# AFE.net
KiCad netlist of a schematic drawn in Altium Designer
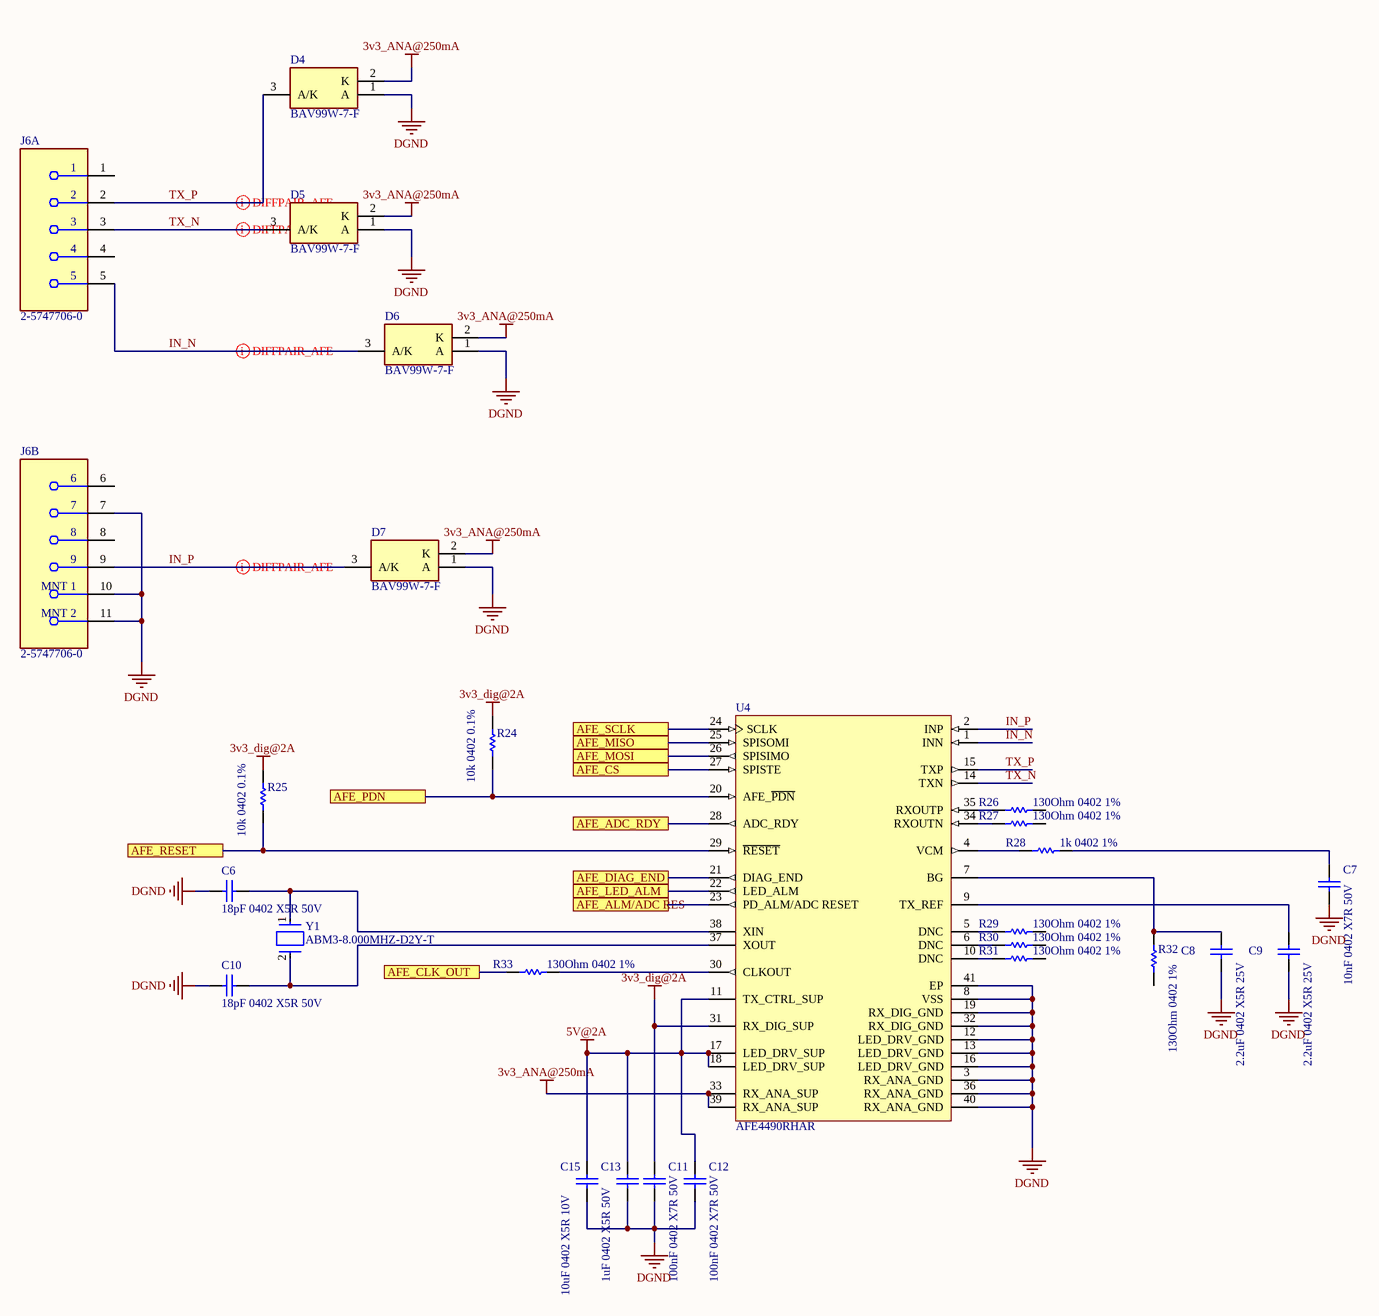
[diagram p0: AFE.SchDoc]

(export (version "E")
  (design (tool "Eeschema 10.0.6"))
  (components
    (comp (ref "C6")
      (value "18pF 0402 X5R 50V")
      (footprint "CAPC1005X55X25NL5T10")
      (libsource (lib "Altium Content Vault") (part "CAP-NP-2"))
    )
    (comp (ref "C7")
      (value "10nF 0402 X7R 50V")
      (footprint "CAPC1005X55X25NL5T10")
      (libsource (lib "Altium Content Vault") (part "CAP-NP-2"))
    )
    (comp (ref "C8")
      (value "2.2uF 0402 X5R 25V")
      (footprint "CAPC1005X55X25NL5T10")
      (libsource (lib "Altium Content Vault") (part "CAP-NP-2"))
    )
    (comp (ref "C9")
      (value "2.2uF 0402 X5R 25V")
      (footprint "CAPC1005X55X25NL5T10")
      (libsource (lib "Altium Content Vault") (part "CAP-NP-2"))
    )
    (comp (ref "C10")
      (value "18pF 0402 X5R 50V")
      (footprint "CAPC1005X55X25NL5T10")
      (libsource (lib "Altium Content Vault") (part "CAP-NP-2"))
    )
    (comp (ref "C11")
      (value "100nF 0402 X7R 50V")
      (footprint "CAPC1005X55X25NL5T10")
      (libsource (lib "Altium Content Vault") (part "CAP-NP-2"))
    )
    (comp (ref "C12")
      (value "100nF 0402 X7R 50V")
      (footprint "CAPC1005X55X25NL5T10")
      (libsource (lib "Altium Content Vault") (part "CAP-NP-2"))
    )
    (comp (ref "C13")
      (value "1uF 0402 X5R 50V")
      (footprint "CAPC1005X55X25NL5T10")
      (libsource (lib "Altium Content Vault") (part "CAP-NP-2"))
    )
    (comp (ref "C15")
      (value "10uF 0402 X5R 10V")
      (footprint "CAPC1005X55X25NL5T10")
      (libsource (lib "Altium Content Vault") (part "CAP-NP-2"))
    )
    (comp (ref "D4")
      (value "BAV99W-7-F")
      (footprint "SamacSys:SOT65P210X110-3N")
      (description "Diode")
      (fields (field (name "MOUSER PART NUMBER") "621-BAV99W-F"))
      (libsource (lib "*") (part "BAV99W-7-F"))
    )
    (comp (ref "D5")
      (value "BAV99W-7-F")
      (footprint "SamacSys:SOT65P210X110-3N")
      (description "Diode")
      (fields (field (name "MOUSER PART NUMBER") "621-BAV99W-F"))
      (libsource (lib "*") (part "BAV99W-7-F"))
    )
    (comp (ref "D6")
      (value "BAV99W-7-F")
      (footprint "SamacSys:SOT65P210X110-3N")
      (description "Diode")
      (fields (field (name "MOUSER PART NUMBER") "621-BAV99W-F"))
      (libsource (lib "*") (part "BAV99W-7-F"))
    )
    (comp (ref "D7")
      (value "BAV99W-7-F")
      (footprint "SamacSys:SOT65P210X110-3N")
      (description "Diode")
      (fields (field (name "MOUSER PART NUMBER") "621-BAV99W-F"))
      (libsource (lib "*") (part "BAV99W-7-F"))
    )
    (comp (ref "J6")
      (value "2-5747706-0")
      (footprint "FP-2-5747706-0-MFG")
      (description "CONN D-SUB RCPT 9POS VERT SOLDER")
      (fields
        (field (name "OCTOPART") "https://octopart.com/2-5747706-0-te+connectivity-39499683")
        (field (name "MANUFACTURER") "TE Connectivity")
      )
      (libsource (lib "Altium Content Vault") (part "05b08df3a4487cf48e63ed58a2c51a6"))
    )
    (comp (ref "R24")
      (value "10k 0402 0.1%")
      (footprint "RESC1005X40X25ML05T10")
      (libsource (lib "Altium Content Vault") (part "RES"))
    )
    (comp (ref "R25")
      (value "10k 0402 0.1%")
      (footprint "RESC1005X40X25ML05T10")
      (libsource (lib "Altium Content Vault") (part "RES"))
    )
    (comp (ref "R26")
      (value "130Ohm 0402 1%")
      (footprint "RESC1005X40X25ML05T10")
      (libsource (lib "Altium Content Vault") (part "RES"))
    )
    (comp (ref "R27")
      (value "130Ohm 0402 1%")
      (footprint "RESC1005X40X25ML05T10")
      (libsource (lib "Altium Content Vault") (part "RES"))
    )
    (comp (ref "R28")
      (value "1k 0402 1%")
      (footprint "RESC1005X40X25ML05T10")
      (libsource (lib "Altium Content Vault") (part "RES"))
    )
    (comp (ref "R29")
      (value "130Ohm 0402 1%")
      (footprint "RESC1005X40X25ML05T10")
      (libsource (lib "Altium Content Vault") (part "RES"))
    )
    (comp (ref "R30")
      (value "130Ohm 0402 1%")
      (footprint "RESC1005X40X25ML05T10")
      (libsource (lib "Altium Content Vault") (part "RES"))
    )
    (comp (ref "R31")
      (value "130Ohm 0402 1%")
      (footprint "RESC1005X40X25ML05T10")
      (libsource (lib "Altium Content Vault") (part "RES"))
    )
    (comp (ref "R32")
      (value "130Ohm 0402 1%")
      (footprint "RESC1005X40X25ML05T10")
      (libsource (lib "Altium Content Vault") (part "RES"))
    )
    (comp (ref "R33")
      (value "130Ohm 0402 1%")
      (footprint "RESC1005X40X25ML05T10")
      (libsource (lib "Altium Content Vault") (part "RES"))
    )
    (comp (ref "U4")
      (value "AFE4490RHAR")
      (footprint "RHA0040B_V")
      (fields (field (name "MANUFACTURER") "Texas Instruments"))
      (libsource (lib "Altium Content Vault") (part "TI-AFE4490-RHA-40"))
    )
    (comp (ref "Y1")
      (value "ABM3-8.000MHZ-D2Y-T")
      (footprint "FP-ABM3-MFG")
      (description "Crystal 8MHz ±20ppm 18pF SMD-2 5mm x 3.2mm")
      (fields (field (name "TOLERANCE") "20ppm"))
      (libsource (lib "Altium Content Vault") (part "c23a69dc6c9e2f18f2079038eb95dd1"))
    )
  )
  (nets
    (net (code "1") (name "/AFE_ADC_RDY") (class "Default")
      (node (ref "U4") (pin "28") (pinfunction "ADC_RDY_28") (pintype "output"))
    )
    (net (code "2") (name "/AFE_ALM{slash}ADC RES") (class "Default")
      (node (ref "U4") (pin "23") (pinfunction "PD_ALM/ADC_RESET_23") (pintype "output"))
    )
    (net (code "3") (name "/AFE_CLK_OUT") (class "Default")
      (node (ref "R33") (pin "2") (pinfunction "2_2") (pintype "passive"))
    )
    (net (code "4") (name "/AFE_CS") (class "Default")
      (node (ref "U4") (pin "27") (pinfunction "SPISTE_27") (pintype "input"))
    )
    (net (code "5") (name "/AFE_DIAG_END") (class "Default")
      (node (ref "U4") (pin "21") (pinfunction "DIAG_END_21") (pintype "output"))
    )
    (net (code "6") (name "/AFE_LED_ALM") (class "Default")
      (node (ref "U4") (pin "22") (pinfunction "LED_ALM_22") (pintype "output"))
    )
    (net (code "7") (name "/AFE_MISO") (class "Default")
      (node (ref "U4") (pin "25") (pinfunction "SPISOMI_25") (pintype "input"))
    )
    (net (code "8") (name "/AFE_MOSI") (class "Default")
      (node (ref "U4") (pin "26") (pinfunction "SPISIMO_26") (pintype "output"))
    )
    (net (code "9") (name "/AFE_PDN") (class "Default")
      (node (ref "R24") (pin "1") (pinfunction "1_1") (pintype "passive"))
      (node (ref "U4") (pin "20") (pinfunction "AFE_~{PDN}_20") (pintype "input"))
    )
    (net (code "10") (name "/AFE_RESET") (class "Default")
      (node (ref "R25") (pin "1") (pinfunction "1_1") (pintype "passive"))
      (node (ref "U4") (pin "29") (pinfunction "~{RESET}_29") (pintype "input"))
    )
    (net (code "11") (name "/AFE_SCLK") (class "Default")
      (node (ref "U4") (pin "24") (pinfunction "SCLK_24") (pintype "input"))
    )
    (net (code "12") (name "/IN_N") (class "Default")
      (node (ref "D6") (pin "3") (pinfunction "A/K_3") (pintype "passive"))
      (node (ref "J6") (pin "5") (pinfunction "5_5") (pintype "passive"))
      (node (ref "U4") (pin "1") (pinfunction "INN_1") (pintype "input"))
    )
    (net (code "13") (name "/IN_P") (class "Default")
      (node (ref "D7") (pin "3") (pinfunction "A/K_3") (pintype "passive"))
      (node (ref "J6") (pin "9") (pinfunction "9_9") (pintype "passive"))
      (node (ref "U4") (pin "2") (pinfunction "INP_2") (pintype "input"))
    )
    (net (code "14") (name "/TX_N") (class "Default")
      (node (ref "D5") (pin "3") (pinfunction "A/K_3") (pintype "passive"))
      (node (ref "J6") (pin "3") (pinfunction "3_3") (pintype "passive"))
      (node (ref "U4") (pin "14") (pinfunction "TXN_14") (pintype "output"))
    )
    (net (code "15") (name "/TX_P") (class "Default")
      (node (ref "D4") (pin "3") (pinfunction "A/K_3") (pintype "passive"))
      (node (ref "J6") (pin "2") (pinfunction "2_2") (pintype "passive"))
      (node (ref "U4") (pin "15") (pinfunction "TXP_15") (pintype "output"))
    )
    (net (code "16") (name "3v3_ANA@250mA") (class "Default")
      (node (ref "D4") (pin "2") (pinfunction "K_2") (pintype "passive"))
      (node (ref "D5") (pin "2") (pinfunction "K_2") (pintype "passive"))
      (node (ref "D6") (pin "2") (pinfunction "K_2") (pintype "passive"))
      (node (ref "D7") (pin "2") (pinfunction "K_2") (pintype "passive"))
      (node (ref "U4") (pin "33") (pinfunction "RX_ANA_SUP_33") (pintype "power_in"))
      (node (ref "U4") (pin "39") (pinfunction "RX_ANA_SUP_39") (pintype "power_in"))
    )
    (net (code "17") (name "3v3_dig@2A") (class "Default")
      (node (ref "C11") (pin "2") (pinfunction "2_2") (pintype "passive"))
      (node (ref "R24") (pin "2") (pinfunction "2_2") (pintype "passive"))
      (node (ref "R25") (pin "2") (pinfunction "2_2") (pintype "passive"))
      (node (ref "U4") (pin "31") (pinfunction "RX_DIG_SUP_31") (pintype "power_in"))
    )
    (net (code "18") (name "5V@2A") (class "Default")
      (node (ref "C12") (pin "2") (pinfunction "2_2") (pintype "passive"))
      (node (ref "C13") (pin "2") (pinfunction "2_2") (pintype "passive"))
      (node (ref "C15") (pin "2") (pinfunction "2_2") (pintype "passive"))
      (node (ref "U4") (pin "11") (pinfunction "TX_CTRL_SUP_11") (pintype "power_in"))
      (node (ref "U4") (pin "17") (pinfunction "LED_DRV_SUP_17") (pintype "power_in"))
      (node (ref "U4") (pin "18") (pinfunction "LED_DRV_SUP_18") (pintype "power_in"))
    )
    (net (code "19") (name "DGND") (class "Default")
      (node (ref "C10") (pin "1") (pinfunction "1_1") (pintype "passive"))
      (node (ref "C11") (pin "1") (pinfunction "1_1") (pintype "passive"))
      (node (ref "C12") (pin "1") (pinfunction "1_1") (pintype "passive"))
      (node (ref "C13") (pin "1") (pinfunction "1_1") (pintype "passive"))
      (node (ref "C15") (pin "1") (pinfunction "1_1") (pintype "passive"))
      (node (ref "C6") (pin "1") (pinfunction "1_1") (pintype "passive"))
      (node (ref "C7") (pin "1") (pinfunction "1_1") (pintype "passive"))
      (node (ref "C8") (pin "1") (pinfunction "1_1") (pintype "passive"))
      (node (ref "C9") (pin "1") (pinfunction "1_1") (pintype "passive"))
      (node (ref "D4") (pin "1") (pinfunction "A_1") (pintype "passive"))
      (node (ref "D5") (pin "1") (pinfunction "A_1") (pintype "passive"))
      (node (ref "D6") (pin "1") (pinfunction "A_1") (pintype "passive"))
      (node (ref "D7") (pin "1") (pinfunction "A_1") (pintype "passive"))
      (node (ref "J6") (pin "10") (pinfunction "MNT_1_10") (pintype "passive"))
      (node (ref "J6") (pin "11") (pinfunction "MNT_2_11") (pintype "passive"))
      (node (ref "J6") (pin "7") (pinfunction "7_7") (pintype "passive"))
      (node (ref "U4") (pin "12") (pinfunction "LED_DRV_GND_12") (pintype "power_in"))
      (node (ref "U4") (pin "13") (pinfunction "LED_DRV_GND_13") (pintype "power_in"))
      (node (ref "U4") (pin "16") (pinfunction "LED_DRV_GND_16") (pintype "power_in"))
      (node (ref "U4") (pin "19") (pinfunction "RX_DIG_GND_19") (pintype "power_in"))
      (node (ref "U4") (pin "3") (pinfunction "RX_ANA_GND_3") (pintype "power_in"))
      (node (ref "U4") (pin "32") (pinfunction "RX_DIG_GND_32") (pintype "power_in"))
      (node (ref "U4") (pin "36") (pinfunction "RX_ANA_GND_36") (pintype "power_in"))
      (node (ref "U4") (pin "40") (pinfunction "RX_ANA_GND_40") (pintype "power_in"))
      (node (ref "U4") (pin "41") (pinfunction "EP_41") (pintype "passive"))
      (node (ref "U4") (pin "8") (pinfunction "VSS_8") (pintype "power_in"))
    )
    (net (code "20") (name "Net-(C7-Pad2)") (class "Default")
      (node (ref "C7") (pin "2") (pinfunction "2_2") (pintype "passive"))
      (node (ref "R28") (pin "1") (pinfunction "1_1") (pintype "passive"))
    )
    (net (code "21") (name "Net-(R29-Pad2)") (class "Default")
      (node (ref "R29") (pin "2") (pinfunction "2_2") (pintype "passive"))
      (node (ref "U4") (pin "5") (pinfunction "DNC_5") (pintype "passive"))
    )
    (net (code "22") (name "Net-(R30-Pad2)") (class "Default")
      (node (ref "R30") (pin "2") (pinfunction "2_2") (pintype "passive"))
      (node (ref "U4") (pin "6") (pinfunction "DNC_6") (pintype "passive"))
    )
    (net (code "23") (name "Net-(R31-Pad2)") (class "Default")
      (node (ref "R31") (pin "2") (pinfunction "2_2") (pintype "passive"))
      (node (ref "U4") (pin "10") (pinfunction "DNC_10") (pintype "passive"))
    )
    (net (code "24") (name "Net-(U4-BG)") (class "Default")
      (node (ref "C8") (pin "2") (pinfunction "2_2") (pintype "passive"))
      (node (ref "R32") (pin "2") (pinfunction "2_2") (pintype "passive"))
      (node (ref "U4") (pin "7") (pinfunction "BG_7") (pintype "passive"))
    )
    (net (code "25") (name "Net-(U4-CLKOUT)") (class "Default")
      (node (ref "R33") (pin "1") (pinfunction "1_1") (pintype "passive"))
      (node (ref "U4") (pin "30") (pinfunction "CLKOUT_30") (pintype "output"))
    )
    (net (code "26") (name "Net-(U4-RXOUTN)") (class "Default")
      (node (ref "R27") (pin "2") (pinfunction "2_2") (pintype "passive"))
      (node (ref "U4") (pin "34") (pinfunction "RXOUTN_34") (pintype "input"))
    )
    (net (code "27") (name "Net-(U4-RXOUTP)") (class "Default")
      (node (ref "R26") (pin "2") (pinfunction "2_2") (pintype "passive"))
      (node (ref "U4") (pin "35") (pinfunction "RXOUTP_35") (pintype "input"))
    )
    (net (code "28") (name "Net-(U4-TX_REF)") (class "Default")
      (node (ref "C9") (pin "2") (pinfunction "2_2") (pintype "passive"))
      (node (ref "U4") (pin "9") (pinfunction "TX_REF_9") (pintype "passive"))
    )
    (net (code "29") (name "Net-(U4-VCM)") (class "Default")
      (node (ref "R28") (pin "2") (pinfunction "2_2") (pintype "passive"))
      (node (ref "U4") (pin "4") (pinfunction "VCM_4") (pintype "output"))
    )
    (net (code "30") (name "Net-(U4-XIN)") (class "Default")
      (node (ref "C6") (pin "2") (pinfunction "2_2") (pintype "passive"))
      (node (ref "U4") (pin "38") (pinfunction "XIN_38") (pintype "passive"))
      (node (ref "Y1") (pin "1") (pinfunction "1_1") (pintype "passive"))
    )
    (net (code "31") (name "Net-(U4-XOUT)") (class "Default")
      (node (ref "C10") (pin "2") (pinfunction "2_2") (pintype "passive"))
      (node (ref "U4") (pin "37") (pinfunction "XOUT_37") (pintype "passive"))
      (node (ref "Y1") (pin "2") (pinfunction "2_2") (pintype "passive"))
    )
    (net (code "32") (name "unconnected-(J6-Pad1)") (class "Default")
      (node (ref "J6") (pin "1") (pinfunction "1_1") (pintype "passive"))
    )
    (net (code "33") (name "unconnected-(J6-Pad4)") (class "Default")
      (node (ref "J6") (pin "4") (pinfunction "4_4") (pintype "passive"))
    )
    (net (code "34") (name "unconnected-(J6-Pad6)") (class "Default")
      (node (ref "J6") (pin "6") (pinfunction "6_6") (pintype "passive"))
    )
    (net (code "35") (name "unconnected-(J6-Pad8)") (class "Default")
      (node (ref "J6") (pin "8") (pinfunction "8_8") (pintype "passive"))
    )
    (net (code "36") (name "unconnected-(R26-Pad1)") (class "Default")
      (node (ref "R26") (pin "1") (pinfunction "1_1") (pintype "passive"))
    )
    (net (code "37") (name "unconnected-(R27-Pad1)") (class "Default")
      (node (ref "R27") (pin "1") (pinfunction "1_1") (pintype "passive"))
    )
    (net (code "38") (name "unconnected-(R29-Pad1)") (class "Default")
      (node (ref "R29") (pin "1") (pinfunction "1_1") (pintype "passive"))
    )
    (net (code "39") (name "unconnected-(R30-Pad1)") (class "Default")
      (node (ref "R30") (pin "1") (pinfunction "1_1") (pintype "passive"))
    )
    (net (code "40") (name "unconnected-(R31-Pad1)") (class "Default")
      (node (ref "R31") (pin "1") (pinfunction "1_1") (pintype "passive"))
    )
    (net (code "41") (name "unconnected-(R32-Pad1)") (class "Default")
      (node (ref "R32") (pin "1") (pinfunction "1_1") (pintype "passive"))
    )
  )
)
